# Monster_Tile.net
KiCad netlist of a schematic drawn in Altium Designer
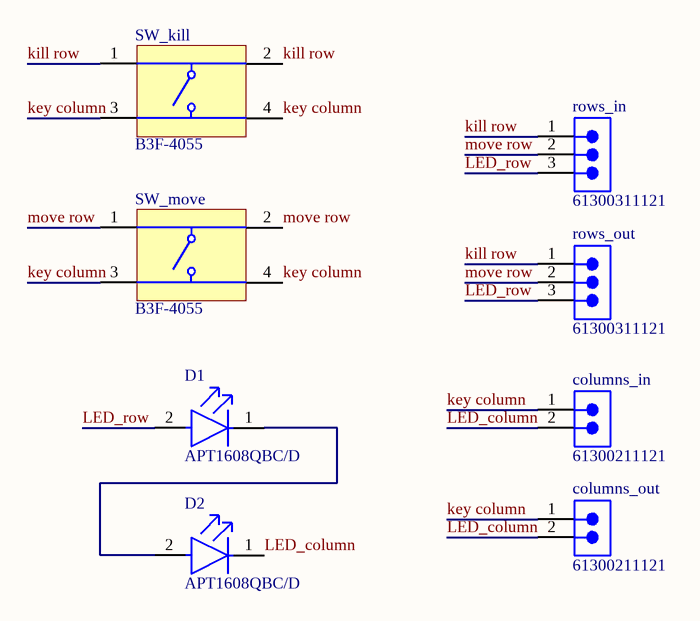
[diagram p0: Monster_Tile.SchDoc]

(export (version "E")
  (design (tool "Eeschema 10.0.6"))
  (components
    (comp (ref "columns_in")
      (value "61300211121")
      (footprint "61300211121")
      (libsource (lib "Altium Content Vault") (part "Header_Male_1R_02P"))
    )
    (comp (ref "columns_out")
      (value "61300211121")
      (footprint "61300211121")
      (libsource (lib "Altium Content Vault") (part "Header_Male_1R_02P"))
    )
    (comp (ref "D1")
      (value "APT1608QBC/D")
      (footprint "FP-APT1608QBC-D-MFG")
      (description "LED BLUE CLEAR CHIP SMD")
      (libsource (lib "Altium Content Vault") (part "8706943c75ba83719d021d2fdc84c58"))
    )
    (comp (ref "D2")
      (value "APT1608QBC/D")
      (footprint "FP-APT1608QBC-D-MFG")
      (description "LED BLUE CLEAR CHIP SMD")
      (libsource (lib "Altium Content Vault") (part "8706943c75ba83719d021d2fdc84c58"))
    )
    (comp (ref "rows_in")
      (value "61300311121")
      (footprint "61300311121")
      (libsource (lib "Altium Content Vault") (part "Header_Male_1R_03P"))
    )
    (comp (ref "rows_out")
      (value "61300311121")
      (footprint "61300311121")
      (libsource (lib "Altium Content Vault") (part "Header_Male_1R_03P"))
    )
    (comp (ref "SW_kill")
      (value "B3F-4055")
      (footprint "OMRON-B3F-4055_V")
      (description "Tactile Switch, 1 to 50 mA, 100 mOhm Max, 5 to 24 VDC, -25 to 70 degC, 4-Pin THD, RoHS, Bulk")
      (fields (field (name "MANUFACTURER") "OmronElectronics"))
      (libsource (lib "Altium Content Vault") (part "SW-SPST-4_A"))
    )
    (comp (ref "SW_move")
      (value "B3F-4055")
      (footprint "OMRON-B3F-4055_V")
      (description "Tactile Switch, 1 to 50 mA, 100 mOhm Max, 5 to 24 VDC, -25 to 70 degC, 4-Pin THD, RoHS, Bulk")
      (fields (field (name "MANUFACTURER") "OmronElectronics"))
      (libsource (lib "Altium Content Vault") (part "SW-SPST-4_A"))
    )
  )
  (nets
    (net (code "1") (name "/LED_column") (class "Default")
      (node (ref "D2") (pin "1") (pinfunction "C_1") (pintype "passive"))
      (node (ref "columns_in") (pin "2") (pinfunction "2_2") (pintype "passive"))
      (node (ref "columns_out") (pin "2") (pinfunction "2_2") (pintype "passive"))
    )
    (net (code "2") (name "/LED_row") (class "Default")
      (node (ref "D1") (pin "2") (pinfunction "A_2") (pintype "passive"))
      (node (ref "rows_in") (pin "3") (pinfunction "3_3") (pintype "passive"))
      (node (ref "rows_out") (pin "3") (pinfunction "3_3") (pintype "passive"))
    )
    (net (code "3") (name "/key column") (class "Default")
      (node (ref "SW_kill") (pin "3") (pinfunction "3_3") (pintype "passive"))
      (node (ref "SW_kill") (pin "4") (pinfunction "4_4") (pintype "passive"))
      (node (ref "SW_move") (pin "3") (pinfunction "3_3") (pintype "passive"))
      (node (ref "SW_move") (pin "4") (pinfunction "4_4") (pintype "passive"))
      (node (ref "columns_in") (pin "1") (pinfunction "1_1") (pintype "passive"))
      (node (ref "columns_out") (pin "1") (pinfunction "1_1") (pintype "passive"))
    )
    (net (code "4") (name "/kill row") (class "Default")
      (node (ref "SW_kill") (pin "1") (pinfunction "1_1") (pintype "passive"))
      (node (ref "SW_kill") (pin "2") (pinfunction "2_2") (pintype "passive"))
      (node (ref "rows_in") (pin "1") (pinfunction "1_1") (pintype "passive"))
      (node (ref "rows_out") (pin "1") (pinfunction "1_1") (pintype "passive"))
    )
    (net (code "5") (name "/move row") (class "Default")
      (node (ref "SW_move") (pin "1") (pinfunction "1_1") (pintype "passive"))
      (node (ref "SW_move") (pin "2") (pinfunction "2_2") (pintype "passive"))
      (node (ref "rows_in") (pin "2") (pinfunction "2_2") (pintype "passive"))
      (node (ref "rows_out") (pin "2") (pinfunction "2_2") (pintype "passive"))
    )
    (net (code "6") (name "Net-(D1-C)") (class "Default")
      (node (ref "D1") (pin "1") (pinfunction "C_1") (pintype "passive"))
      (node (ref "D2") (pin "2") (pinfunction "A_2") (pintype "passive"))
    )
  )
)
